# SparkFun-Wearable-Shield-For-Photon.net
KiCad netlist of a schematic drawn in EAGLE
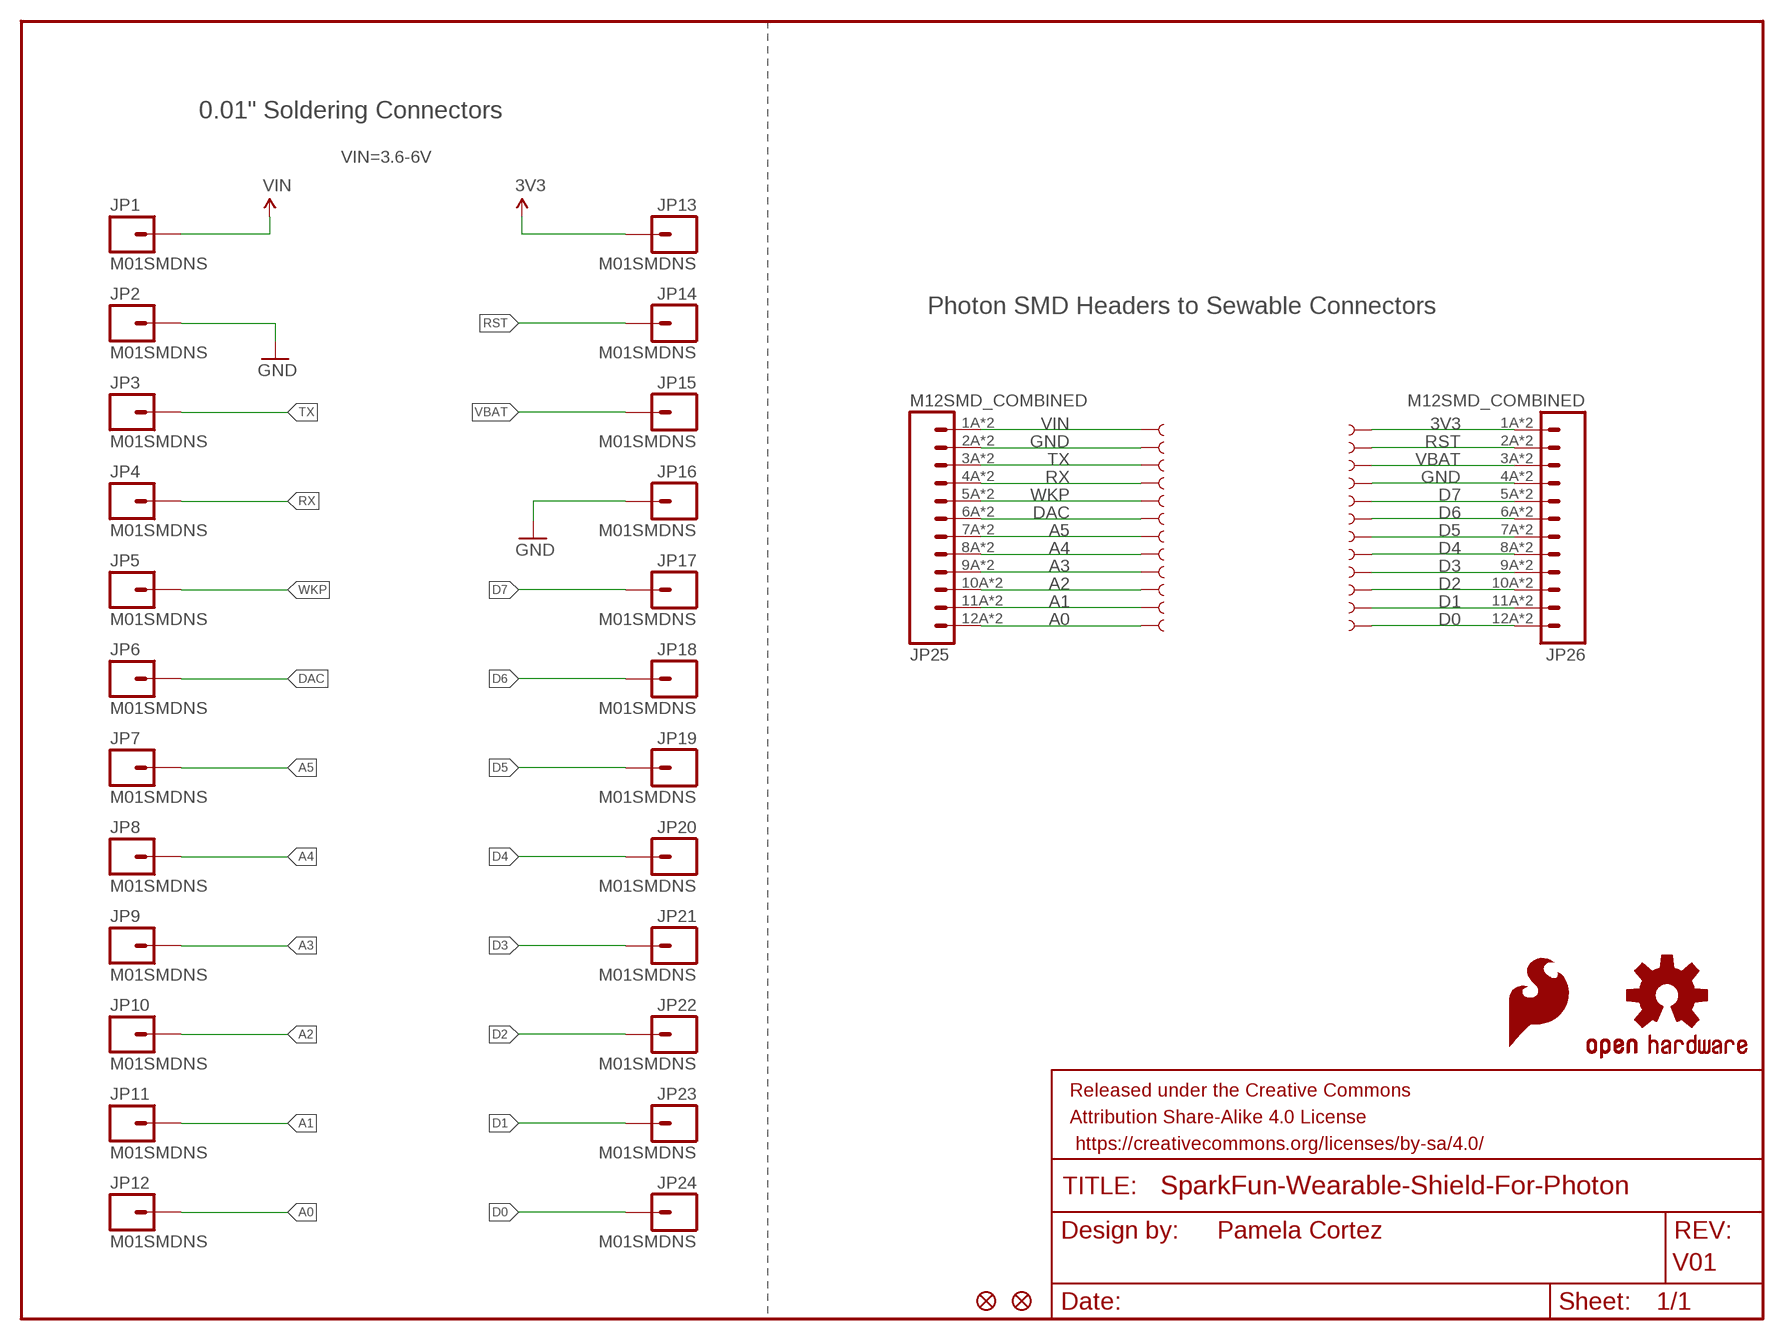
[diagram p0: schematic, sheet 1]

(export (version "E")
  (design (tool "Eeschema 10.0.6"))
  (components
    (comp (ref "FID1")
      (value "FIDUCIAL1X2")
      (footprint "eagle-import:FIDUCIAL-1X2")
      (libsource (lib "eagle-import") (part "FIDUCIAL1X2"))
    )
    (comp (ref "FID2")
      (value "FIDUCIAL1X2")
      (footprint "eagle-import:FIDUCIAL-1X2")
      (libsource (lib "eagle-import") (part "FIDUCIAL1X2"))
    )
    (comp (ref "FRAME1")
      (value "FRAME-LETTER")
      (footprint "eagle-import:CREATIVE_COMMONS")
      (fields (field (name "DESIGNER") "NAME"))
      (libsource (lib "eagle-import") (part "FRAME-LETTER"))
    )
    (comp (ref "J1")
      (value "PAD")
      (footprint "eagle-import:PAD-LONG-2-SIDED")
      (libsource (lib "eagle-import") (part "PAD"))
    )
    (comp (ref "J2")
      (value "PAD")
      (footprint "eagle-import:PAD-LONG-2-SIDED")
      (libsource (lib "eagle-import") (part "PAD"))
    )
    (comp (ref "J3")
      (value "PAD")
      (footprint "eagle-import:PAD-LONG-2-SIDED")
      (libsource (lib "eagle-import") (part "PAD"))
    )
    (comp (ref "J4")
      (value "PAD")
      (footprint "eagle-import:PAD-LONG-2-SIDED")
      (libsource (lib "eagle-import") (part "PAD"))
    )
    (comp (ref "J5")
      (value "PAD")
      (footprint "eagle-import:PAD-LONG-2-SIDED")
      (libsource (lib "eagle-import") (part "PAD"))
    )
    (comp (ref "J6")
      (value "PAD")
      (footprint "eagle-import:PAD-LONG-2-SIDED")
      (libsource (lib "eagle-import") (part "PAD"))
    )
    (comp (ref "J7")
      (value "PAD")
      (footprint "eagle-import:PAD-LONG-2-SIDED")
      (libsource (lib "eagle-import") (part "PAD"))
    )
    (comp (ref "J8")
      (value "PAD")
      (footprint "eagle-import:PAD-LONG-2-SIDED")
      (libsource (lib "eagle-import") (part "PAD"))
    )
    (comp (ref "J9")
      (value "PAD")
      (footprint "eagle-import:PAD-LONG-2-SIDED")
      (libsource (lib "eagle-import") (part "PAD"))
    )
    (comp (ref "J10")
      (value "PAD")
      (footprint "eagle-import:PAD-LONG-2-SIDED")
      (libsource (lib "eagle-import") (part "PAD"))
    )
    (comp (ref "J11")
      (value "PAD")
      (footprint "eagle-import:PAD-LONG-2-SIDED")
      (libsource (lib "eagle-import") (part "PAD"))
    )
    (comp (ref "J12")
      (value "PAD")
      (footprint "eagle-import:PAD-LONG-2-SIDED")
      (libsource (lib "eagle-import") (part "PAD"))
    )
    (comp (ref "J13")
      (value "PAD")
      (footprint "eagle-import:PAD-LONG-2-SIDED")
      (libsource (lib "eagle-import") (part "PAD"))
    )
    (comp (ref "J14")
      (value "PAD")
      (footprint "eagle-import:PAD-LONG-2-SIDED")
      (libsource (lib "eagle-import") (part "PAD"))
    )
    (comp (ref "J15")
      (value "PAD")
      (footprint "eagle-import:PAD-LONG-2-SIDED")
      (libsource (lib "eagle-import") (part "PAD"))
    )
    (comp (ref "J16")
      (value "PAD")
      (footprint "eagle-import:PAD-LONG-2-SIDED")
      (libsource (lib "eagle-import") (part "PAD"))
    )
    (comp (ref "J17")
      (value "PAD")
      (footprint "eagle-import:PAD-LONG-2-SIDED")
      (libsource (lib "eagle-import") (part "PAD"))
    )
    (comp (ref "J18")
      (value "PAD")
      (footprint "eagle-import:PAD-LONG-2-SIDED")
      (libsource (lib "eagle-import") (part "PAD"))
    )
    (comp (ref "J19")
      (value "PAD")
      (footprint "eagle-import:PAD-LONG-2-SIDED")
      (libsource (lib "eagle-import") (part "PAD"))
    )
    (comp (ref "J20")
      (value "PAD")
      (footprint "eagle-import:PAD-LONG-2-SIDED")
      (libsource (lib "eagle-import") (part "PAD"))
    )
    (comp (ref "J21")
      (value "PAD")
      (footprint "eagle-import:PAD-LONG-2-SIDED")
      (libsource (lib "eagle-import") (part "PAD"))
    )
    (comp (ref "J22")
      (value "PAD")
      (footprint "eagle-import:PAD-LONG-2-SIDED")
      (libsource (lib "eagle-import") (part "PAD"))
    )
    (comp (ref "J23")
      (value "PAD")
      (footprint "eagle-import:PAD-LONG-2-SIDED")
      (libsource (lib "eagle-import") (part "PAD"))
    )
    (comp (ref "J24")
      (value "PAD")
      (footprint "eagle-import:PAD-LONG-2-SIDED")
      (libsource (lib "eagle-import") (part "PAD"))
    )
    (comp (ref "JP1")
      (value "M01SMDNS")
      (footprint "eagle-import:1X01NS")
      (libsource (lib "eagle-import") (part "M01SMDNS"))
    )
    (comp (ref "JP2")
      (value "M01SMDNS")
      (footprint "eagle-import:1X01NS")
      (libsource (lib "eagle-import") (part "M01SMDNS"))
    )
    (comp (ref "JP3")
      (value "M01SMDNS")
      (footprint "eagle-import:1X01NS")
      (libsource (lib "eagle-import") (part "M01SMDNS"))
    )
    (comp (ref "JP4")
      (value "M01SMDNS")
      (footprint "eagle-import:1X01NS")
      (libsource (lib "eagle-import") (part "M01SMDNS"))
    )
    (comp (ref "JP5")
      (value "M01SMDNS")
      (footprint "eagle-import:1X01NS")
      (libsource (lib "eagle-import") (part "M01SMDNS"))
    )
    (comp (ref "JP6")
      (value "M01SMDNS")
      (footprint "eagle-import:1X01NS")
      (libsource (lib "eagle-import") (part "M01SMDNS"))
    )
    (comp (ref "JP7")
      (value "M01SMDNS")
      (footprint "eagle-import:1X01NS")
      (libsource (lib "eagle-import") (part "M01SMDNS"))
    )
    (comp (ref "JP8")
      (value "M01SMDNS")
      (footprint "eagle-import:1X01NS")
      (libsource (lib "eagle-import") (part "M01SMDNS"))
    )
    (comp (ref "JP9")
      (value "M01SMDNS")
      (footprint "eagle-import:1X01NS")
      (libsource (lib "eagle-import") (part "M01SMDNS"))
    )
    (comp (ref "JP10")
      (value "M01SMDNS")
      (footprint "eagle-import:1X01NS")
      (libsource (lib "eagle-import") (part "M01SMDNS"))
    )
    (comp (ref "JP11")
      (value "M01SMDNS")
      (footprint "eagle-import:1X01NS")
      (libsource (lib "eagle-import") (part "M01SMDNS"))
    )
    (comp (ref "JP12")
      (value "M01SMDNS")
      (footprint "eagle-import:1X01NS")
      (libsource (lib "eagle-import") (part "M01SMDNS"))
    )
    (comp (ref "JP13")
      (value "M01SMDNS")
      (footprint "eagle-import:1X01NS")
      (libsource (lib "eagle-import") (part "M01SMDNS"))
    )
    (comp (ref "JP14")
      (value "M01SMDNS")
      (footprint "eagle-import:1X01NS")
      (libsource (lib "eagle-import") (part "M01SMDNS"))
    )
    (comp (ref "JP15")
      (value "M01SMDNS")
      (footprint "eagle-import:1X01NS")
      (libsource (lib "eagle-import") (part "M01SMDNS"))
    )
    (comp (ref "JP16")
      (value "M01SMDNS")
      (footprint "eagle-import:1X01NS")
      (libsource (lib "eagle-import") (part "M01SMDNS"))
    )
    (comp (ref "JP17")
      (value "M01SMDNS")
      (footprint "eagle-import:1X01NS")
      (libsource (lib "eagle-import") (part "M01SMDNS"))
    )
    (comp (ref "JP18")
      (value "M01SMDNS")
      (footprint "eagle-import:1X01NS")
      (libsource (lib "eagle-import") (part "M01SMDNS"))
    )
    (comp (ref "JP19")
      (value "M01SMDNS")
      (footprint "eagle-import:1X01NS")
      (libsource (lib "eagle-import") (part "M01SMDNS"))
    )
    (comp (ref "JP20")
      (value "M01SMDNS")
      (footprint "eagle-import:1X01NS")
      (libsource (lib "eagle-import") (part "M01SMDNS"))
    )
    (comp (ref "JP21")
      (value "M01SMDNS")
      (footprint "eagle-import:1X01NS")
      (libsource (lib "eagle-import") (part "M01SMDNS"))
    )
    (comp (ref "JP22")
      (value "M01SMDNS")
      (footprint "eagle-import:1X01NS")
      (libsource (lib "eagle-import") (part "M01SMDNS"))
    )
    (comp (ref "JP23")
      (value "M01SMDNS")
      (footprint "eagle-import:1X01NS")
      (libsource (lib "eagle-import") (part "M01SMDNS"))
    )
    (comp (ref "JP24")
      (value "M01SMDNS")
      (footprint "eagle-import:1X01NS")
      (libsource (lib "eagle-import") (part "M01SMDNS"))
    )
    (comp (ref "JP25")
      (value "M12SMD_COMBINED")
      (footprint "eagle-import:1X12_SMD_COMBINED")
      (libsource (lib "eagle-import") (part "M12SMD_COMBINED"))
    )
    (comp (ref "JP26")
      (value "M12SMD_COMBINED")
      (footprint "eagle-import:1X12_SMD_COMBINED")
      (libsource (lib "eagle-import") (part "M12SMD_COMBINED"))
    )
    (comp (ref "LOGO1")
      (value "SFE_LOGO_FLAME.2_INCH")
      (footprint "eagle-import:SFE_LOGO_FLAME_.2")
      (libsource (lib "eagle-import") (part "SFE_LOGO_FLAME.2_INCH"))
    )
    (comp (ref "LOGO2")
      (value "OSHW-LOGOM")
      (footprint "eagle-import:OSHW-LOGO-M")
      (libsource (lib "eagle-import") (part "OSHW-LOGOM"))
    )
  )
  (nets
    (net (code "1") (name "3V3") (class "Default")
      (node (ref "J13") (pin "1") (pinfunction "1_1") (pintype "bidirectional"))
      (node (ref "JP13") (pin "1") (pinfunction "1_1") (pintype "passive"))
      (node (ref "JP26") (pin "1A") (pinfunction "1_1A") (pintype "passive"))
      (node (ref "JP26") (pin "1B") (pinfunction "1_1B") (pintype "passive"))
    )
    (net (code "2") (name "A0") (class "Default")
      (node (ref "J12") (pin "1") (pinfunction "1_1") (pintype "bidirectional"))
      (node (ref "JP12") (pin "1") (pinfunction "1_1") (pintype "passive"))
      (node (ref "JP25") (pin "12A") (pinfunction "12_12A") (pintype "passive"))
      (node (ref "JP25") (pin "12B") (pinfunction "12_12B") (pintype "passive"))
    )
    (net (code "3") (name "A1") (class "Default")
      (node (ref "J11") (pin "1") (pinfunction "1_1") (pintype "bidirectional"))
      (node (ref "JP11") (pin "1") (pinfunction "1_1") (pintype "passive"))
      (node (ref "JP25") (pin "11A") (pinfunction "11_11A") (pintype "passive"))
      (node (ref "JP25") (pin "11B") (pinfunction "11_11B") (pintype "passive"))
    )
    (net (code "4") (name "A2") (class "Default")
      (node (ref "J10") (pin "1") (pinfunction "1_1") (pintype "bidirectional"))
      (node (ref "JP10") (pin "1") (pinfunction "1_1") (pintype "passive"))
      (node (ref "JP25") (pin "10A") (pinfunction "10_10A") (pintype "passive"))
      (node (ref "JP25") (pin "10B") (pinfunction "10_10B") (pintype "passive"))
    )
    (net (code "5") (name "A3") (class "Default")
      (node (ref "J9") (pin "1") (pinfunction "1_1") (pintype "bidirectional"))
      (node (ref "JP25") (pin "9A") (pinfunction "9_9A") (pintype "passive"))
      (node (ref "JP25") (pin "9B") (pinfunction "9_9B") (pintype "passive"))
      (node (ref "JP9") (pin "1") (pinfunction "1_1") (pintype "passive"))
    )
    (net (code "6") (name "A4") (class "Default")
      (node (ref "J8") (pin "1") (pinfunction "1_1") (pintype "bidirectional"))
      (node (ref "JP25") (pin "8A") (pinfunction "8_8A") (pintype "passive"))
      (node (ref "JP25") (pin "8B") (pinfunction "8_8B") (pintype "passive"))
      (node (ref "JP8") (pin "1") (pinfunction "1_1") (pintype "passive"))
    )
    (net (code "7") (name "A5") (class "Default")
      (node (ref "J7") (pin "1") (pinfunction "1_1") (pintype "bidirectional"))
      (node (ref "JP25") (pin "7A") (pinfunction "7_7A") (pintype "passive"))
      (node (ref "JP25") (pin "7B") (pinfunction "7_7B") (pintype "passive"))
      (node (ref "JP7") (pin "1") (pinfunction "1_1") (pintype "passive"))
    )
    (net (code "8") (name "D0") (class "Default")
      (node (ref "J24") (pin "1") (pinfunction "1_1") (pintype "bidirectional"))
      (node (ref "JP24") (pin "1") (pinfunction "1_1") (pintype "passive"))
      (node (ref "JP26") (pin "12A") (pinfunction "12_12A") (pintype "passive"))
      (node (ref "JP26") (pin "12B") (pinfunction "12_12B") (pintype "passive"))
    )
    (net (code "9") (name "D1") (class "Default")
      (node (ref "J23") (pin "1") (pinfunction "1_1") (pintype "bidirectional"))
      (node (ref "JP23") (pin "1") (pinfunction "1_1") (pintype "passive"))
      (node (ref "JP26") (pin "11A") (pinfunction "11_11A") (pintype "passive"))
      (node (ref "JP26") (pin "11B") (pinfunction "11_11B") (pintype "passive"))
    )
    (net (code "10") (name "D2") (class "Default")
      (node (ref "J22") (pin "1") (pinfunction "1_1") (pintype "bidirectional"))
      (node (ref "JP22") (pin "1") (pinfunction "1_1") (pintype "passive"))
      (node (ref "JP26") (pin "10A") (pinfunction "10_10A") (pintype "passive"))
      (node (ref "JP26") (pin "10B") (pinfunction "10_10B") (pintype "passive"))
    )
    (net (code "11") (name "D3") (class "Default")
      (node (ref "J21") (pin "1") (pinfunction "1_1") (pintype "bidirectional"))
      (node (ref "JP21") (pin "1") (pinfunction "1_1") (pintype "passive"))
      (node (ref "JP26") (pin "9A") (pinfunction "9_9A") (pintype "passive"))
      (node (ref "JP26") (pin "9B") (pinfunction "9_9B") (pintype "passive"))
    )
    (net (code "12") (name "D4") (class "Default")
      (node (ref "J20") (pin "1") (pinfunction "1_1") (pintype "bidirectional"))
      (node (ref "JP20") (pin "1") (pinfunction "1_1") (pintype "passive"))
      (node (ref "JP26") (pin "8A") (pinfunction "8_8A") (pintype "passive"))
      (node (ref "JP26") (pin "8B") (pinfunction "8_8B") (pintype "passive"))
    )
    (net (code "13") (name "D5") (class "Default")
      (node (ref "J19") (pin "1") (pinfunction "1_1") (pintype "bidirectional"))
      (node (ref "JP19") (pin "1") (pinfunction "1_1") (pintype "passive"))
      (node (ref "JP26") (pin "7A") (pinfunction "7_7A") (pintype "passive"))
      (node (ref "JP26") (pin "7B") (pinfunction "7_7B") (pintype "passive"))
    )
    (net (code "14") (name "D6") (class "Default")
      (node (ref "J18") (pin "1") (pinfunction "1_1") (pintype "bidirectional"))
      (node (ref "JP18") (pin "1") (pinfunction "1_1") (pintype "passive"))
      (node (ref "JP26") (pin "6A") (pinfunction "6_6A") (pintype "passive"))
      (node (ref "JP26") (pin "6B") (pinfunction "6_6B") (pintype "passive"))
    )
    (net (code "15") (name "D7") (class "Default")
      (node (ref "J17") (pin "1") (pinfunction "1_1") (pintype "bidirectional"))
      (node (ref "JP17") (pin "1") (pinfunction "1_1") (pintype "passive"))
      (node (ref "JP26") (pin "5A") (pinfunction "5_5A") (pintype "passive"))
      (node (ref "JP26") (pin "5B") (pinfunction "5_5B") (pintype "passive"))
    )
    (net (code "16") (name "DAC") (class "Default")
      (node (ref "J6") (pin "1") (pinfunction "1_1") (pintype "bidirectional"))
      (node (ref "JP25") (pin "6A") (pinfunction "6_6A") (pintype "passive"))
      (node (ref "JP25") (pin "6B") (pinfunction "6_6B") (pintype "passive"))
      (node (ref "JP6") (pin "1") (pinfunction "1_1") (pintype "passive"))
    )
    (net (code "17") (name "GND") (class "Default")
      (node (ref "J16") (pin "1") (pinfunction "1_1") (pintype "bidirectional"))
      (node (ref "J2") (pin "1") (pinfunction "1_1") (pintype "bidirectional"))
      (node (ref "JP16") (pin "1") (pinfunction "1_1") (pintype "passive"))
      (node (ref "JP2") (pin "1") (pinfunction "1_1") (pintype "passive"))
      (node (ref "JP25") (pin "2A") (pinfunction "2_2A") (pintype "passive"))
      (node (ref "JP25") (pin "2B") (pinfunction "2_2B") (pintype "passive"))
      (node (ref "JP26") (pin "4A") (pinfunction "4_4A") (pintype "passive"))
      (node (ref "JP26") (pin "4B") (pinfunction "4_4B") (pintype "passive"))
    )
    (net (code "18") (name "RST") (class "Default")
      (node (ref "J14") (pin "1") (pinfunction "1_1") (pintype "bidirectional"))
      (node (ref "JP14") (pin "1") (pinfunction "1_1") (pintype "passive"))
      (node (ref "JP26") (pin "2A") (pinfunction "2_2A") (pintype "passive"))
      (node (ref "JP26") (pin "2B") (pinfunction "2_2B") (pintype "passive"))
    )
    (net (code "19") (name "RX") (class "Default")
      (node (ref "J4") (pin "1") (pinfunction "1_1") (pintype "bidirectional"))
      (node (ref "JP25") (pin "4A") (pinfunction "4_4A") (pintype "passive"))
      (node (ref "JP25") (pin "4B") (pinfunction "4_4B") (pintype "passive"))
      (node (ref "JP4") (pin "1") (pinfunction "1_1") (pintype "passive"))
    )
    (net (code "20") (name "TX") (class "Default")
      (node (ref "J3") (pin "1") (pinfunction "1_1") (pintype "bidirectional"))
      (node (ref "JP25") (pin "3A") (pinfunction "3_3A") (pintype "passive"))
      (node (ref "JP25") (pin "3B") (pinfunction "3_3B") (pintype "passive"))
      (node (ref "JP3") (pin "1") (pinfunction "1_1") (pintype "passive"))
    )
    (net (code "21") (name "VBAT") (class "Default")
      (node (ref "J15") (pin "1") (pinfunction "1_1") (pintype "bidirectional"))
      (node (ref "JP15") (pin "1") (pinfunction "1_1") (pintype "passive"))
      (node (ref "JP26") (pin "3A") (pinfunction "3_3A") (pintype "passive"))
      (node (ref "JP26") (pin "3B") (pinfunction "3_3B") (pintype "passive"))
    )
    (net (code "22") (name "VIN") (class "Default")
      (node (ref "J1") (pin "1") (pinfunction "1_1") (pintype "bidirectional"))
      (node (ref "JP1") (pin "1") (pinfunction "1_1") (pintype "passive"))
      (node (ref "JP25") (pin "1A") (pinfunction "1_1A") (pintype "passive"))
      (node (ref "JP25") (pin "1B") (pinfunction "1_1B") (pintype "passive"))
    )
    (net (code "23") (name "WKP") (class "Default")
      (node (ref "J5") (pin "1") (pinfunction "1_1") (pintype "bidirectional"))
      (node (ref "JP25") (pin "5A") (pinfunction "5_5A") (pintype "passive"))
      (node (ref "JP25") (pin "5B") (pinfunction "5_5B") (pintype "passive"))
      (node (ref "JP5") (pin "1") (pinfunction "1_1") (pintype "passive"))
    )
  )
)
